# V1_0.net
KiCad netlist of a schematic drawn in Altium Designer
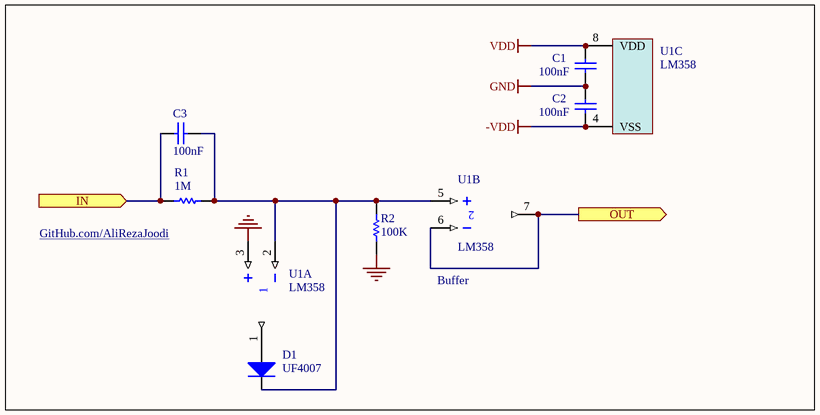
[diagram p0: V1.0.SchDoc]

(export (version "E")
  (design (tool "Eeschema 10.0.6"))
  (components
    (comp (ref "C1")
      (value "100nF")
      (footprint "CAPNTO2.54-3.05x1.78A")
      (description "Capacitor")
      (fields (field (name "MANUFACTURER") "Generic Components") (field (name "PUBLISHER") "Altium Limited"))
      (libsource (lib "Miscellaneous Devices") (part "Cap"))
    )
    (comp (ref "C2")
      (value "100nF")
      (footprint "CAPNTO2.54-3.05x1.78A")
      (description "Capacitor")
      (fields (field (name "MANUFACTURER") "Generic Components") (field (name "PUBLISHER") "Altium Limited"))
      (libsource (lib "Miscellaneous Devices") (part "Cap"))
    )
    (comp (ref "C3")
      (value "100nF")
      (footprint "CAPNTO2.54-3.05x1.78A")
      (description "Capacitor")
      (fields (field (name "MANUFACTURER") "Generic Components") (field (name "PUBLISHER") "Altium Limited"))
      (libsource (lib "Miscellaneous Devices") (part "Cap"))
    )
    (comp (ref "D1")
      (value "UF4007")
      (footprint "DIODE-0.4")
      (description "Default Diode")
      (fields (field (name "MANUFACTURER") "Generic Components") (field (name "PUBLISHER") "Altium Limited"))
      (libsource (lib "Miscellaneous Devices") (part "Diode"))
    )
    (comp (ref "R1")
      (value "1M")
      (footprint "AXIAL-0.4")
      (description "Resistor")
      (fields (field (name "PUBLISHER") "Altium Limited"))
      (libsource (lib "Miscellaneous Devices") (part "Res1"))
    )
    (comp (ref "R2")
      (value "100K")
      (footprint "AXIAL-0.4")
      (description "Resistor")
      (fields (field (name "PUBLISHER") "Altium Limited"))
      (libsource (lib "Miscellaneous Devices") (part "Res1"))
    )
    (comp (ref "U1")
      (value "LM358")
      (footprint "DIP8")
      (description "Dual Low-Power Operational Amplifier")
      (fields (field (name "PUBLISHER") "Altium Limited"))
      (libsource (lib "my Libraries") (part "LM358"))
    )
  )
  (nets
    (net (code "1") (name "-VDD") (class "Default")
      (node (ref "C2") (pin "2") (pinfunction "2_2") (pintype "passive"))
      (node (ref "U1") (pin "4") (pinfunction "VSS_4") (pintype "power_in"))
    )
    (net (code "2") (name "/IN") (class "Default")
      (node (ref "C3") (pin "2") (pinfunction "2_2") (pintype "passive"))
      (node (ref "R1") (pin "2") (pinfunction "2_2") (pintype "passive"))
    )
    (net (code "3") (name "/OUT") (class "Default")
      (node (ref "U1") (pin "6") (pinfunction "IN-_6") (pintype "input"))
      (node (ref "U1") (pin "7") (pinfunction "OUT_7") (pintype "output"))
    )
    (net (code "4") (name "GND") (class "Default")
      (node (ref "C1") (pin "2") (pinfunction "2_2") (pintype "passive"))
      (node (ref "C2") (pin "1") (pinfunction "1_1") (pintype "passive"))
      (node (ref "R2") (pin "2") (pinfunction "2_2") (pintype "passive"))
      (node (ref "U1") (pin "3") (pinfunction "IN+_3") (pintype "input"))
    )
    (net (code "5") (name "Net-(D1-A)") (class "Default")
      (node (ref "D1") (pin "1") (pinfunction "A_1") (pintype "passive"))
      (node (ref "U1") (pin "1") (pinfunction "OUT_1") (pintype "output"))
    )
    (net (code "6") (name "Net-(D1-K)") (class "Default")
      (node (ref "C3") (pin "1") (pinfunction "1_1") (pintype "passive"))
      (node (ref "D1") (pin "2") (pinfunction "K_2") (pintype "passive"))
      (node (ref "R1") (pin "1") (pinfunction "1_1") (pintype "passive"))
      (node (ref "R2") (pin "1") (pinfunction "1_1") (pintype "passive"))
      (node (ref "U1") (pin "2") (pinfunction "IN-_2") (pintype "input"))
      (node (ref "U1") (pin "5") (pinfunction "IN+_5") (pintype "input"))
    )
    (net (code "7") (name "VDD") (class "Default")
      (node (ref "C1") (pin "1") (pinfunction "1_1") (pintype "passive"))
      (node (ref "U1") (pin "8") (pinfunction "VDD_8") (pintype "passive"))
    )
  )
)
